# MIDDLE_LAYER.net
KiCad netlist of a schematic drawn in Altium Designer
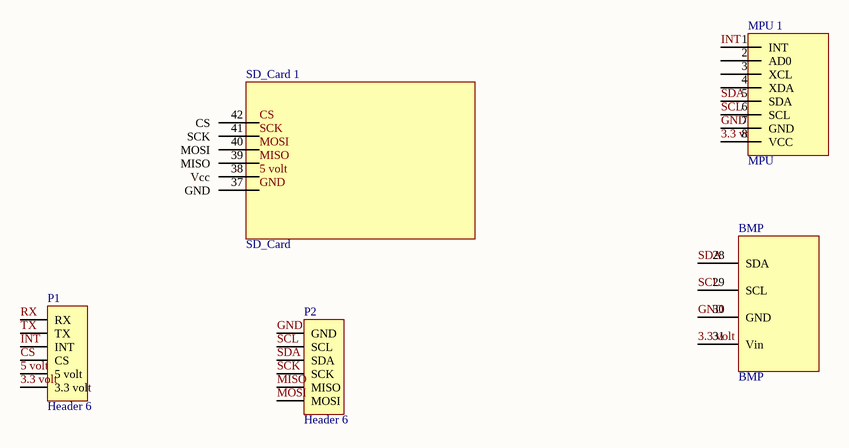
[diagram p0: MIDDLE LAYER.SchDoc]

(export (version "E")
  (design (tool "Eeschema 10.0.6"))
  (components
    (comp (ref "BMP") (value "BMP") (footprint "BMP") (libsource (lib "bmb") (part "BMP")))
    (comp (ref "MPU 1") (value "MPU") (footprint "MPU") (libsource (lib "MPU") (part "MPU")))
    (comp (ref "P1")
      (value "Header 6")
      (footprint "HDR1X6")
      (description "Header, 6-Pin")
      (fields (field (name "PUBLISHER") "Altium Limited"))
      (libsource (lib "Miscellaneous Connectors") (part "Header 6"))
    )
    (comp (ref "P2")
      (value "Header 6")
      (footprint "HDR1X6")
      (description "Header, 6-Pin")
      (fields (field (name "PUBLISHER") "Altium Limited"))
      (libsource (lib "Miscellaneous Connectors") (part "Header 6"))
    )
    (comp (ref "SD_Card 1")
      (value "SD_Card")
      (footprint "SD_Card")
      (libsource (lib "SD_Card") (part "SD_Card"))
    )
  )
  (nets
    (net (code "1") (name "/3.3 volt") (class "Default")
      (node (ref "BMP") (pin "31") (pinfunction "Vin_31") (pintype "passive"))
      (node (ref "MPU 1") (pin "8") (pinfunction "VCC_8") (pintype "passive"))
      (node (ref "P1") (pin "6") (pinfunction "3.3_volt_6") (pintype "passive"))
    )
    (net (code "2") (name "/5 volt") (class "Default")
      (node (ref "P1") (pin "5") (pinfunction "5_volt_5") (pintype "passive"))
      (node (ref "SD_Card 1") (pin "38") (pinfunction "Vcc_38") (pintype "passive"))
    )
    (net (code "3") (name "/CS") (class "Default")
      (node (ref "P1") (pin "4") (pinfunction "CS_4") (pintype "passive"))
      (node (ref "SD_Card 1") (pin "42") (pinfunction "CS_42") (pintype "passive"))
    )
    (net (code "4") (name "/GND") (class "Default")
      (node (ref "BMP") (pin "30") (pinfunction "GND_30") (pintype "passive"))
      (node (ref "MPU 1") (pin "7") (pinfunction "GND_7") (pintype "passive"))
      (node (ref "P2") (pin "1") (pinfunction "RX_1") (pintype "passive"))
      (node (ref "SD_Card 1") (pin "37") (pinfunction "GND_37") (pintype "passive"))
    )
    (net (code "5") (name "/INT") (class "Default")
      (node (ref "MPU 1") (pin "1") (pinfunction "INT_1") (pintype "passive"))
      (node (ref "P1") (pin "3") (pinfunction "INT_3") (pintype "passive"))
    )
    (net (code "6") (name "/MISO") (class "Default")
      (node (ref "P2") (pin "5") (pinfunction "5_volt_5") (pintype "passive"))
      (node (ref "SD_Card 1") (pin "39") (pinfunction "MISO_39") (pintype "passive"))
    )
    (net (code "7") (name "/MOSI") (class "Default")
      (node (ref "P2") (pin "6") (pinfunction "3.3_volt_6") (pintype "passive"))
      (node (ref "SD_Card 1") (pin "40") (pinfunction "MOSI_40") (pintype "passive"))
    )
    (net (code "8") (name "/RX") (class "Default")
      (node (ref "P1") (pin "1") (pinfunction "RX_1") (pintype "passive"))
    )
    (net (code "9") (name "/SCK") (class "Default")
      (node (ref "P2") (pin "4") (pinfunction "CS_4") (pintype "passive"))
      (node (ref "SD_Card 1") (pin "41") (pinfunction "SCK_41") (pintype "passive"))
    )
    (net (code "10") (name "/SCL") (class "Default")
      (node (ref "BMP") (pin "29") (pinfunction "SCL_29") (pintype "passive"))
      (node (ref "MPU 1") (pin "6") (pinfunction "SCL_6") (pintype "passive"))
      (node (ref "P2") (pin "2") (pinfunction "TX_2") (pintype "passive"))
    )
    (net (code "11") (name "/SDA") (class "Default")
      (node (ref "BMP") (pin "28") (pinfunction "SDA_28") (pintype "passive"))
      (node (ref "MPU 1") (pin "5") (pinfunction "SDA_5") (pintype "passive"))
      (node (ref "P2") (pin "3") (pinfunction "INT_3") (pintype "passive"))
    )
    (net (code "12") (name "/TX") (class "Default")
      (node (ref "P1") (pin "2") (pinfunction "TX_2") (pintype "passive"))
    )
    (net (code "13") (name "unconnected-(MPU 1-AD0-Pad2)") (class "Default")
      (node (ref "MPU 1") (pin "2") (pinfunction "AD0_2") (pintype "passive"))
    )
    (net (code "14") (name "unconnected-(MPU 1-XCL-Pad3)") (class "Default")
      (node (ref "MPU 1") (pin "3") (pinfunction "XCL_3") (pintype "passive"))
    )
    (net (code "15") (name "unconnected-(MPU 1-XDA-Pad4)") (class "Default")
      (node (ref "MPU 1") (pin "4") (pinfunction "XDA_4") (pintype "passive"))
    )
  )
)
